# 48V_to_BOB.net
KiCad netlist of a schematic drawn in Altium Designer
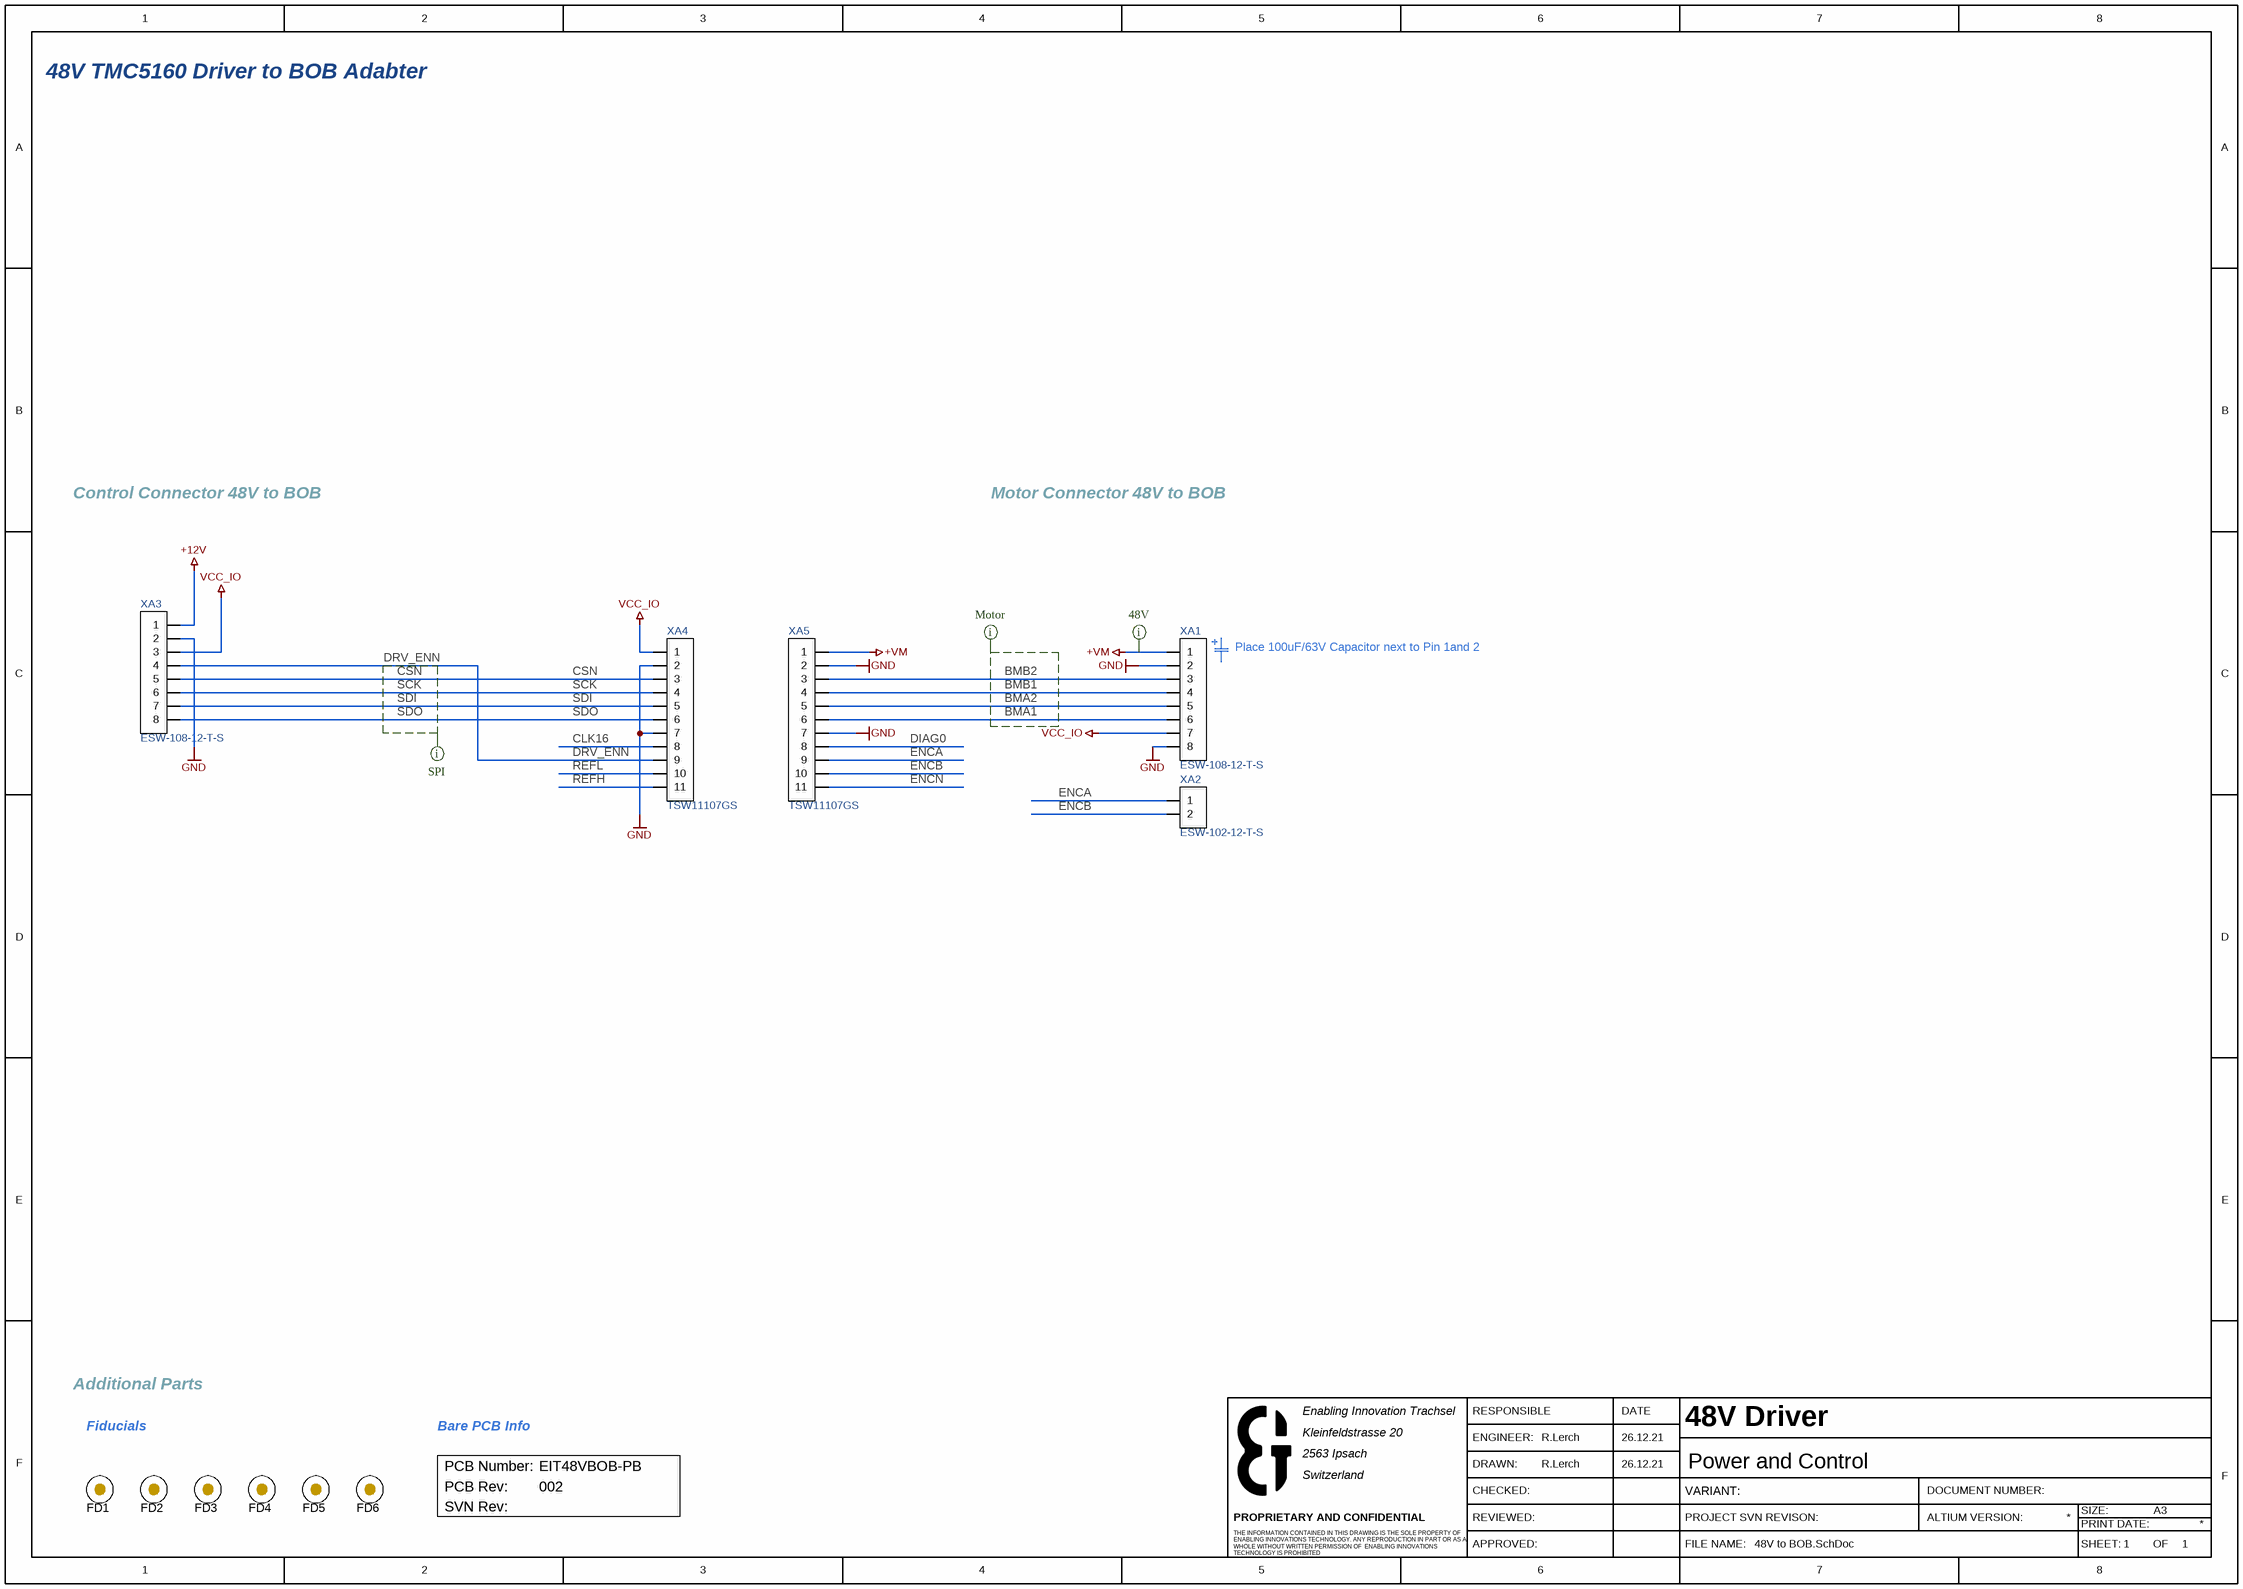
[diagram p0: 48V to BOB.SchDoc]

(export (version "E")
  (design (tool "Eeschema 10.0.6"))
  (components
    (comp (ref "=Artikel_Stamm+'-'+Typ_PB")
      (value "Printed Circuit Board")
      (description "Bare PCB")
      (fields (field (name "MANUFACTURER") "Any"))
      (libsource (lib "48V to BOB") (part "Bare PCB"))
    )
    (comp (ref "FD1")
      (value "Fiducial Mark")
      (footprint "Fiducial")
      (description "Fiducial mark.  There is nothing to buy or mount.")
      (libsource (lib "48V to BOB") (part "CMP-013-00002-0"))
    )
    (comp (ref "FD2")
      (value "Fiducial Mark")
      (footprint "Fiducial")
      (description "Fiducial mark.  There is nothing to buy or mount.")
      (libsource (lib "48V to BOB") (part "CMP-013-00002-0"))
    )
    (comp (ref "FD3")
      (value "Fiducial Mark")
      (footprint "Fiducial")
      (description "Fiducial mark.  There is nothing to buy or mount.")
      (libsource (lib "48V to BOB") (part "CMP-013-00002-0"))
    )
    (comp (ref "FD4")
      (value "Fiducial Mark")
      (footprint "Fiducial")
      (description "Fiducial mark.  There is nothing to buy or mount.")
      (libsource (lib "48V to BOB") (part "CMP-013-00002-0"))
    )
    (comp (ref "FD5")
      (value "Fiducial Mark")
      (footprint "Fiducial")
      (description "Fiducial mark.  There is nothing to buy or mount.")
      (libsource (lib "48V to BOB") (part "CMP-013-00002-0"))
    )
    (comp (ref "FD6")
      (value "Fiducial Mark")
      (footprint "Fiducial")
      (description "Fiducial mark.  There is nothing to buy or mount.")
      (libsource (lib "48V to BOB") (part "CMP-013-00002-0"))
    )
    (comp (ref "XA1")
      (value "ESW-108-12-T-S")
      (footprint "SAMTEC_ESW-108-12-T-S")
      (description "Con Socket PCB SMD 8Pos 2.54mm")
      (fields
        (field (name "PART NUMBER") "13-0359")
        (field (name "VOLTAGE") "250V")
        (field (name "AUTHOR") "Lerch")
      )
      (libsource (lib "") (part "CMP-008-00005-0_1"))
    )
    (comp (ref "XA2")
      (value "ESW-102-12-T-S")
      (footprint "SAMTEC_ESW-102-12-G-S")
      (description "Con Socket PCB SMD 2Pos 2.54mm")
      (fields (field (name "VOLTAGE") "250V") (field (name "AUTHOR") "Lerch"))
      (libsource (lib "48V to BOB") (part "CMP-008-00004-0"))
    )
    (comp (ref "XA3")
      (value "ESW-108-12-T-S")
      (footprint "SAMTEC_ESW-108-12-T-S")
      (description "Con Socket PCB SMD 8Pos 2.54mm")
      (fields
        (field (name "PART NUMBER") "13-0359")
        (field (name "VOLTAGE") "250V")
        (field (name "AUTHOR") "Lerch")
      )
      (libsource (lib "48V to BOB") (part "CMP-008-00005-0"))
    )
    (comp (ref "XA4")
      (value "TSW11107GS")
      (footprint "SAMTEC_TSW-111-07-G-S")
      (description "Con Header PCB SMD 11Pos 2.54mm")
      (fields (field (name "VOLTAGE") "250V") (field (name "AUTHOR") "Lerch"))
      (libsource (lib "") (part "CMP-008-00003-0_1"))
    )
    (comp (ref "XA5")
      (value "TSW11107GS")
      (footprint "SAMTEC_TSW-111-07-G-S")
      (description "Con Header PCB SMD 11Pos 2.54mm")
      (fields (field (name "VOLTAGE") "250V") (field (name "AUTHOR") "Lerch"))
      (libsource (lib "48V to BOB") (part "CMP-008-00003-0"))
    )
  )
  (nets
    (net (code "1") (name "+12V") (class "Default")
      (node (ref "XA3") (pin "1") (pinfunction "1_1") (pintype "passive"))
    )
    (net (code "2") (name "+VM") (class "Default")
      (node (ref "XA1") (pin "1") (pinfunction "1_1") (pintype "passive"))
      (node (ref "XA5") (pin "1") (pinfunction "1_1") (pintype "passive"))
    )
    (net (code "3") (name "/BMA1") (class "Default")
      (node (ref "XA1") (pin "6") (pinfunction "6_6") (pintype "passive"))
      (node (ref "XA5") (pin "6") (pinfunction "6_6") (pintype "passive"))
    )
    (net (code "4") (name "/BMA2") (class "Default")
      (node (ref "XA1") (pin "5") (pinfunction "5_5") (pintype "passive"))
      (node (ref "XA5") (pin "5") (pinfunction "5_5") (pintype "passive"))
    )
    (net (code "5") (name "/BMB1") (class "Default")
      (node (ref "XA1") (pin "4") (pinfunction "4_4") (pintype "passive"))
      (node (ref "XA5") (pin "4") (pinfunction "4_4") (pintype "passive"))
    )
    (net (code "6") (name "/BMB2") (class "Default")
      (node (ref "XA1") (pin "3") (pinfunction "3_3") (pintype "passive"))
      (node (ref "XA5") (pin "3") (pinfunction "3_3") (pintype "passive"))
    )
    (net (code "7") (name "/CLK16") (class "Default")
      (node (ref "XA4") (pin "8") (pinfunction "8_8") (pintype "passive"))
    )
    (net (code "8") (name "/CSN") (class "Default")
      (node (ref "XA3") (pin "5") (pinfunction "5_5") (pintype "passive"))
      (node (ref "XA4") (pin "3") (pinfunction "3_3") (pintype "passive"))
    )
    (net (code "9") (name "/DIAG0") (class "Default")
      (node (ref "XA5") (pin "8") (pinfunction "8_8") (pintype "passive"))
    )
    (net (code "10") (name "/DRV_ENN") (class "Default")
      (node (ref "XA3") (pin "4") (pinfunction "4_4") (pintype "passive"))
      (node (ref "XA4") (pin "9") (pinfunction "9_9") (pintype "passive"))
    )
    (net (code "11") (name "/ENCA") (class "Default")
      (node (ref "XA2") (pin "1") (pinfunction "1_1") (pintype "passive"))
      (node (ref "XA5") (pin "9") (pinfunction "9_9") (pintype "passive"))
    )
    (net (code "12") (name "/ENCB") (class "Default")
      (node (ref "XA2") (pin "2") (pinfunction "2_2") (pintype "passive"))
      (node (ref "XA5") (pin "10") (pinfunction "10_10") (pintype "passive"))
    )
    (net (code "13") (name "/ENCN") (class "Default")
      (node (ref "XA5") (pin "11") (pinfunction "11_11") (pintype "passive"))
    )
    (net (code "14") (name "/REFH") (class "Default")
      (node (ref "XA4") (pin "11") (pinfunction "11_11") (pintype "passive"))
    )
    (net (code "15") (name "/REFL") (class "Default")
      (node (ref "XA4") (pin "10") (pinfunction "10_10") (pintype "passive"))
    )
    (net (code "16") (name "/SCK") (class "Default")
      (node (ref "XA3") (pin "6") (pinfunction "6_6") (pintype "passive"))
      (node (ref "XA4") (pin "4") (pinfunction "4_4") (pintype "passive"))
    )
    (net (code "17") (name "/SDI") (class "Default")
      (node (ref "XA3") (pin "7") (pinfunction "7_7") (pintype "passive"))
      (node (ref "XA4") (pin "5") (pinfunction "5_5") (pintype "passive"))
    )
    (net (code "18") (name "/SDO") (class "Default")
      (node (ref "XA3") (pin "8") (pinfunction "8_8") (pintype "passive"))
      (node (ref "XA4") (pin "6") (pinfunction "6_6") (pintype "passive"))
    )
    (net (code "19") (name "GND") (class "Default")
      (node (ref "XA1") (pin "2") (pinfunction "2_2") (pintype "passive"))
      (node (ref "XA1") (pin "8") (pinfunction "8_8") (pintype "passive"))
      (node (ref "XA3") (pin "2") (pinfunction "2_2") (pintype "passive"))
      (node (ref "XA4") (pin "2") (pinfunction "2_2") (pintype "passive"))
      (node (ref "XA4") (pin "7") (pinfunction "7_7") (pintype "passive"))
      (node (ref "XA5") (pin "2") (pinfunction "2_2") (pintype "passive"))
      (node (ref "XA5") (pin "7") (pinfunction "7_7") (pintype "passive"))
    )
    (net (code "20") (name "VCC_IO") (class "Default")
      (node (ref "XA1") (pin "7") (pinfunction "7_7") (pintype "passive"))
      (node (ref "XA3") (pin "3") (pinfunction "3_3") (pintype "passive"))
      (node (ref "XA4") (pin "1") (pinfunction "1_1") (pintype "passive"))
    )
  )
)
